# minidoxs.net
KiCad netlist of a schematic drawn in EAGLE
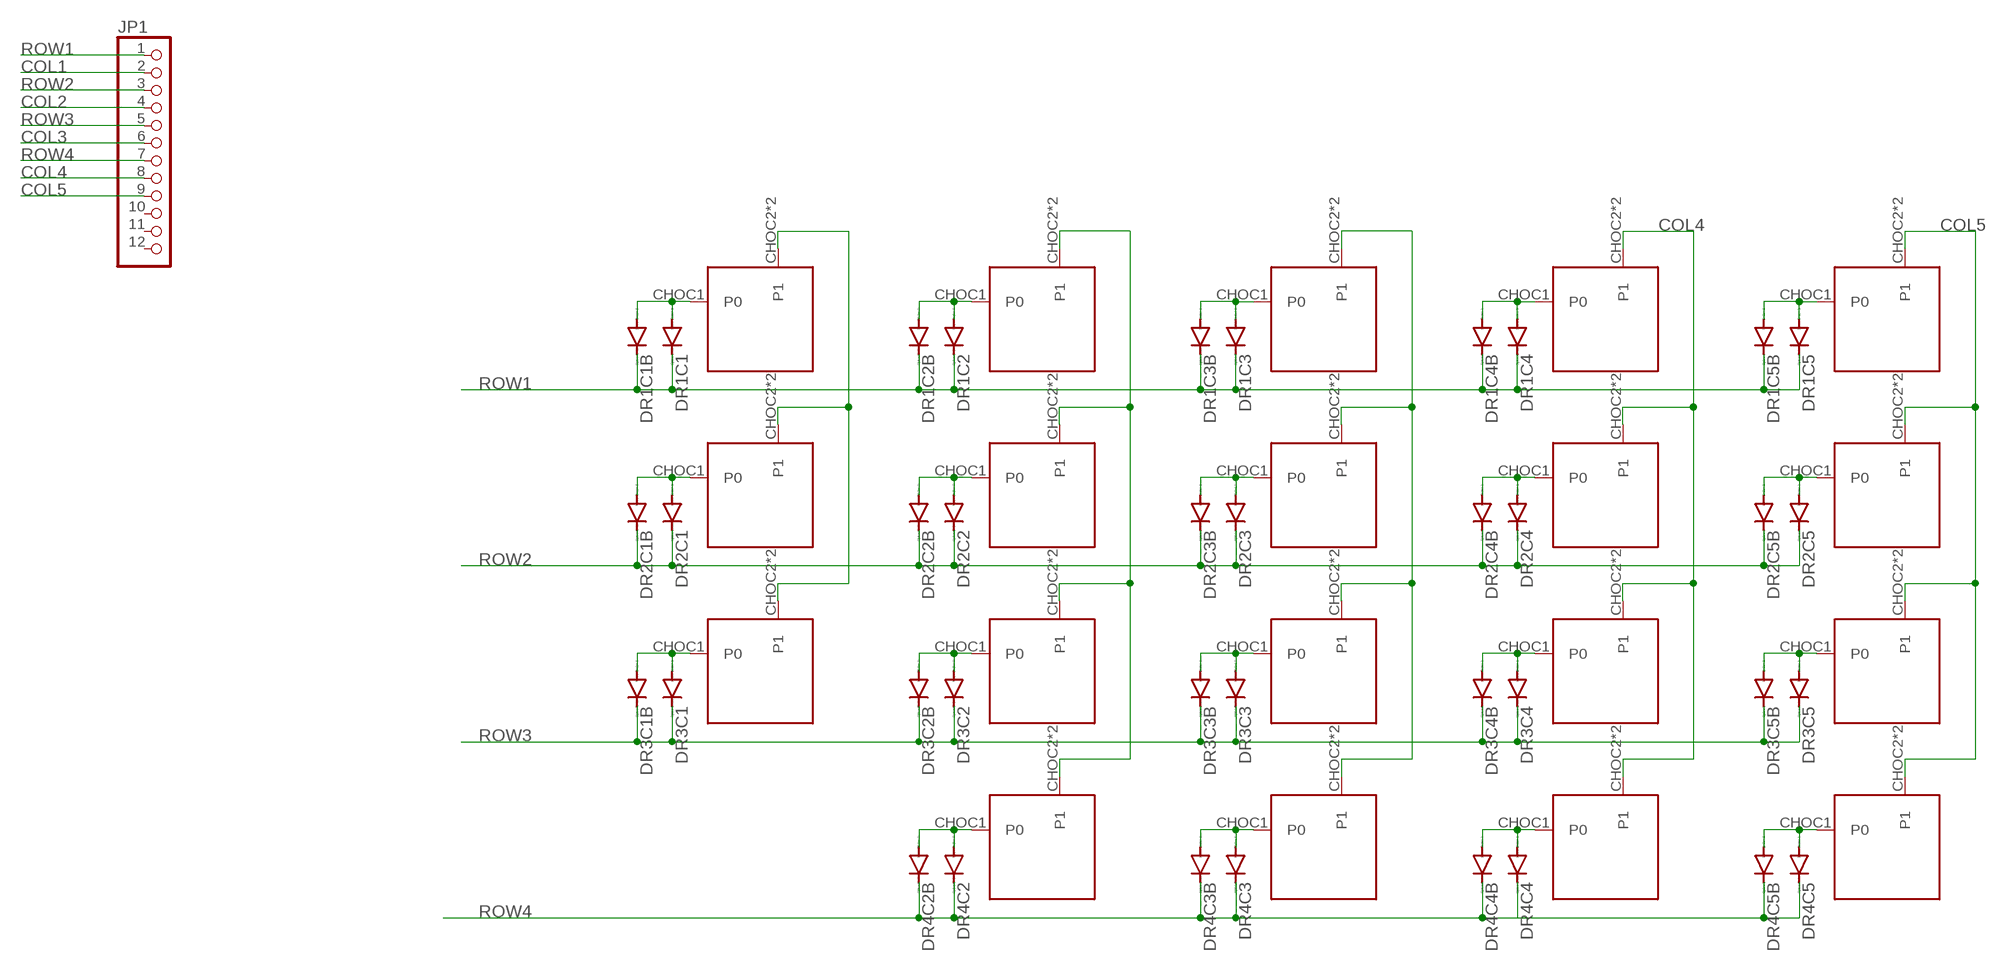
[diagram p0: schematic, sheet 1]

(export (version "E")
  (design (tool "Eeschema 10.0.6"))
  (components
    (comp (ref "DR1C1")
      (value "MBR0520LT")
      (footprint "eagle-import:SOD123")
      (libsource (lib "eagle-import") (part "MBR0520LT"))
    )
    (comp (ref "DR1C1B")
      (value "MBR0520LT")
      (footprint "eagle-import:SOD123")
      (libsource (lib "eagle-import") (part "MBR0520LT"))
    )
    (comp (ref "DR1C2")
      (value "MBR0520LT")
      (footprint "eagle-import:SOD123")
      (libsource (lib "eagle-import") (part "MBR0520LT"))
    )
    (comp (ref "DR1C2B")
      (value "MBR0520LT")
      (footprint "eagle-import:SOD123")
      (libsource (lib "eagle-import") (part "MBR0520LT"))
    )
    (comp (ref "DR1C3")
      (value "MBR0520LT")
      (footprint "eagle-import:SOD123")
      (libsource (lib "eagle-import") (part "MBR0520LT"))
    )
    (comp (ref "DR1C3B")
      (value "MBR0520LT")
      (footprint "eagle-import:SOD123")
      (libsource (lib "eagle-import") (part "MBR0520LT"))
    )
    (comp (ref "DR1C4")
      (value "MBR0520LT")
      (footprint "eagle-import:SOD123")
      (libsource (lib "eagle-import") (part "MBR0520LT"))
    )
    (comp (ref "DR1C4B")
      (value "MBR0520LT")
      (footprint "eagle-import:SOD123")
      (libsource (lib "eagle-import") (part "MBR0520LT"))
    )
    (comp (ref "DR1C5")
      (value "MBR0520LT")
      (footprint "eagle-import:SOD123")
      (libsource (lib "eagle-import") (part "MBR0520LT"))
    )
    (comp (ref "DR1C5B")
      (value "MBR0520LT")
      (footprint "eagle-import:SOD123")
      (libsource (lib "eagle-import") (part "MBR0520LT"))
    )
    (comp (ref "DR2C1")
      (value "MBR0520LT")
      (footprint "eagle-import:SOD123")
      (libsource (lib "eagle-import") (part "MBR0520LT"))
    )
    (comp (ref "DR2C1B")
      (value "MBR0520LT")
      (footprint "eagle-import:SOD123")
      (libsource (lib "eagle-import") (part "MBR0520LT"))
    )
    (comp (ref "DR2C2")
      (value "MBR0520LT")
      (footprint "eagle-import:SOD123")
      (libsource (lib "eagle-import") (part "MBR0520LT"))
    )
    (comp (ref "DR2C2B")
      (value "MBR0520LT")
      (footprint "eagle-import:SOD123")
      (libsource (lib "eagle-import") (part "MBR0520LT"))
    )
    (comp (ref "DR2C3")
      (value "MBR0520LT")
      (footprint "eagle-import:SOD123")
      (libsource (lib "eagle-import") (part "MBR0520LT"))
    )
    (comp (ref "DR2C3B")
      (value "MBR0520LT")
      (footprint "eagle-import:SOD123")
      (libsource (lib "eagle-import") (part "MBR0520LT"))
    )
    (comp (ref "DR2C4")
      (value "MBR0520LT")
      (footprint "eagle-import:SOD123")
      (libsource (lib "eagle-import") (part "MBR0520LT"))
    )
    (comp (ref "DR2C4B")
      (value "MBR0520LT")
      (footprint "eagle-import:SOD123")
      (libsource (lib "eagle-import") (part "MBR0520LT"))
    )
    (comp (ref "DR2C5")
      (value "MBR0520LT")
      (footprint "eagle-import:SOD123")
      (libsource (lib "eagle-import") (part "MBR0520LT"))
    )
    (comp (ref "DR2C5B")
      (value "MBR0520LT")
      (footprint "eagle-import:SOD123")
      (libsource (lib "eagle-import") (part "MBR0520LT"))
    )
    (comp (ref "DR3C1")
      (value "MBR0520LT")
      (footprint "eagle-import:SOD123")
      (libsource (lib "eagle-import") (part "MBR0520LT"))
    )
    (comp (ref "DR3C1B")
      (value "MBR0520LT")
      (footprint "eagle-import:SOD123")
      (libsource (lib "eagle-import") (part "MBR0520LT"))
    )
    (comp (ref "DR3C2")
      (value "MBR0520LT")
      (footprint "eagle-import:SOD123")
      (libsource (lib "eagle-import") (part "MBR0520LT"))
    )
    (comp (ref "DR3C2B")
      (value "MBR0520LT")
      (footprint "eagle-import:SOD123")
      (libsource (lib "eagle-import") (part "MBR0520LT"))
    )
    (comp (ref "DR3C3")
      (value "MBR0520LT")
      (footprint "eagle-import:SOD123")
      (libsource (lib "eagle-import") (part "MBR0520LT"))
    )
    (comp (ref "DR3C3B")
      (value "MBR0520LT")
      (footprint "eagle-import:SOD123")
      (libsource (lib "eagle-import") (part "MBR0520LT"))
    )
    (comp (ref "DR3C4")
      (value "MBR0520LT")
      (footprint "eagle-import:SOD123")
      (libsource (lib "eagle-import") (part "MBR0520LT"))
    )
    (comp (ref "DR3C4B")
      (value "MBR0520LT")
      (footprint "eagle-import:SOD123")
      (libsource (lib "eagle-import") (part "MBR0520LT"))
    )
    (comp (ref "DR3C5")
      (value "MBR0520LT")
      (footprint "eagle-import:SOD123")
      (libsource (lib "eagle-import") (part "MBR0520LT"))
    )
    (comp (ref "DR3C5B")
      (value "MBR0520LT")
      (footprint "eagle-import:SOD123")
      (libsource (lib "eagle-import") (part "MBR0520LT"))
    )
    (comp (ref "DR4C2")
      (value "MBR0520LT")
      (footprint "eagle-import:SOD123")
      (libsource (lib "eagle-import") (part "MBR0520LT"))
    )
    (comp (ref "DR4C2B")
      (value "MBR0520LT")
      (footprint "eagle-import:SOD123")
      (libsource (lib "eagle-import") (part "MBR0520LT"))
    )
    (comp (ref "DR4C3")
      (value "MBR0520LT")
      (footprint "eagle-import:SOD123")
      (libsource (lib "eagle-import") (part "MBR0520LT"))
    )
    (comp (ref "DR4C3B")
      (value "MBR0520LT")
      (footprint "eagle-import:SOD123")
      (libsource (lib "eagle-import") (part "MBR0520LT"))
    )
    (comp (ref "DR4C4")
      (value "MBR0520LT")
      (footprint "eagle-import:SOD123")
      (libsource (lib "eagle-import") (part "MBR0520LT"))
    )
    (comp (ref "DR4C4B")
      (value "MBR0520LT")
      (footprint "eagle-import:SOD123")
      (libsource (lib "eagle-import") (part "MBR0520LT"))
    )
    (comp (ref "DR4C5")
      (value "MBR0520LT")
      (footprint "eagle-import:SOD123")
      (libsource (lib "eagle-import") (part "MBR0520LT"))
    )
    (comp (ref "DR4C5B")
      (value "MBR0520LT")
      (footprint "eagle-import:SOD123")
      (libsource (lib "eagle-import") (part "MBR0520LT"))
    )
    (comp (ref "JP1")
      (value "PINHD-1X12")
      (footprint "eagle-import:1X12")
      (libsource (lib "eagle-import") (part "PINHD-1X12"))
    )
    (comp (ref "U$R1C1")
      (value "KEYSWITCH-PLAIN-CHOC-1U")
      (footprint "eagle-import:CHOC-1U")
      (libsource (lib "eagle-import") (part "KEYSWITCH-PLAIN-CHOC-1U"))
    )
    (comp (ref "U$R1C2")
      (value "KEYSWITCH-PLAIN-CHOC-1U")
      (footprint "eagle-import:CHOC-1U")
      (libsource (lib "eagle-import") (part "KEYSWITCH-PLAIN-CHOC-1U"))
    )
    (comp (ref "U$R1C3")
      (value "KEYSWITCH-PLAIN-CHOC-1U")
      (footprint "eagle-import:CHOC-1U")
      (libsource (lib "eagle-import") (part "KEYSWITCH-PLAIN-CHOC-1U"))
    )
    (comp (ref "U$R1C4")
      (value "KEYSWITCH-PLAIN-CHOC-1U")
      (footprint "eagle-import:CHOC-1U")
      (libsource (lib "eagle-import") (part "KEYSWITCH-PLAIN-CHOC-1U"))
    )
    (comp (ref "U$R1C5")
      (value "KEYSWITCH-PLAIN-CHOC-1U")
      (footprint "eagle-import:CHOC-1U")
      (libsource (lib "eagle-import") (part "KEYSWITCH-PLAIN-CHOC-1U"))
    )
    (comp (ref "U$R2C1")
      (value "KEYSWITCH-PLAIN-CHOC-1U")
      (footprint "eagle-import:CHOC-1U")
      (libsource (lib "eagle-import") (part "KEYSWITCH-PLAIN-CHOC-1U"))
    )
    (comp (ref "U$R2C2")
      (value "KEYSWITCH-PLAIN-CHOC-1U")
      (footprint "eagle-import:CHOC-1U")
      (libsource (lib "eagle-import") (part "KEYSWITCH-PLAIN-CHOC-1U"))
    )
    (comp (ref "U$R2C3")
      (value "KEYSWITCH-PLAIN-CHOC-1U")
      (footprint "eagle-import:CHOC-1U")
      (libsource (lib "eagle-import") (part "KEYSWITCH-PLAIN-CHOC-1U"))
    )
    (comp (ref "U$R2C4")
      (value "KEYSWITCH-PLAIN-CHOC-1U")
      (footprint "eagle-import:CHOC-1U")
      (libsource (lib "eagle-import") (part "KEYSWITCH-PLAIN-CHOC-1U"))
    )
    (comp (ref "U$R2C5")
      (value "KEYSWITCH-PLAIN-CHOC-1U")
      (footprint "eagle-import:CHOC-1U")
      (libsource (lib "eagle-import") (part "KEYSWITCH-PLAIN-CHOC-1U"))
    )
    (comp (ref "U$R3C1")
      (value "KEYSWITCH-PLAIN-CHOC-1U")
      (footprint "eagle-import:CHOC-1U")
      (libsource (lib "eagle-import") (part "KEYSWITCH-PLAIN-CHOC-1U"))
    )
    (comp (ref "U$R3C2")
      (value "KEYSWITCH-PLAIN-CHOC-1U")
      (footprint "eagle-import:CHOC-1U")
      (libsource (lib "eagle-import") (part "KEYSWITCH-PLAIN-CHOC-1U"))
    )
    (comp (ref "U$R3C3")
      (value "KEYSWITCH-PLAIN-CHOC-1U")
      (footprint "eagle-import:CHOC-1U")
      (libsource (lib "eagle-import") (part "KEYSWITCH-PLAIN-CHOC-1U"))
    )
    (comp (ref "U$R3C4")
      (value "KEYSWITCH-PLAIN-CHOC-1U")
      (footprint "eagle-import:CHOC-1U")
      (libsource (lib "eagle-import") (part "KEYSWITCH-PLAIN-CHOC-1U"))
    )
    (comp (ref "U$R3C5")
      (value "KEYSWITCH-PLAIN-CHOC-1U")
      (footprint "eagle-import:CHOC-1U")
      (libsource (lib "eagle-import") (part "KEYSWITCH-PLAIN-CHOC-1U"))
    )
    (comp (ref "U$R4C2")
      (value "KEYSWITCH-PLAIN-CHOC-1U")
      (footprint "eagle-import:CHOC-1U")
      (libsource (lib "eagle-import") (part "KEYSWITCH-PLAIN-CHOC-1U"))
    )
    (comp (ref "U$R4C3")
      (value "KEYSWITCH-PLAIN-CHOC-1U")
      (footprint "eagle-import:CHOC-1U")
      (libsource (lib "eagle-import") (part "KEYSWITCH-PLAIN-CHOC-1U"))
    )
    (comp (ref "U$R4C4")
      (value "KEYSWITCH-PLAIN-CHOC-1U")
      (footprint "eagle-import:CHOC-1U")
      (libsource (lib "eagle-import") (part "KEYSWITCH-PLAIN-CHOC-1U"))
    )
    (comp (ref "U$R4C5")
      (value "KEYSWITCH-PLAIN-CHOC-1U")
      (footprint "eagle-import:CHOC-1U")
      (libsource (lib "eagle-import") (part "KEYSWITCH-PLAIN-CHOC-1U"))
    )
  )
  (nets
    (net (code "1") (name "/COL1") (class "Default")
      (node (ref "JP1") (pin "2") (pinfunction "2_2") (pintype "passive"))
      (node (ref "U$R1C1") (pin "CHOC2") (pinfunction "P1_CHOC2") (pintype "bidirectional"))
      (node (ref "U$R1C1") (pin "CHOC3") (pinfunction "P1_CHOC3") (pintype "bidirectional"))
      (node (ref "U$R2C1") (pin "CHOC2") (pinfunction "P1_CHOC2") (pintype "bidirectional"))
      (node (ref "U$R2C1") (pin "CHOC3") (pinfunction "P1_CHOC3") (pintype "bidirectional"))
      (node (ref "U$R3C1") (pin "CHOC2") (pinfunction "P1_CHOC2") (pintype "bidirectional"))
      (node (ref "U$R3C1") (pin "CHOC3") (pinfunction "P1_CHOC3") (pintype "bidirectional"))
    )
    (net (code "2") (name "/COL2") (class "Default")
      (node (ref "JP1") (pin "4") (pinfunction "4_4") (pintype "passive"))
      (node (ref "U$R1C2") (pin "CHOC2") (pinfunction "P1_CHOC2") (pintype "bidirectional"))
      (node (ref "U$R1C2") (pin "CHOC3") (pinfunction "P1_CHOC3") (pintype "bidirectional"))
      (node (ref "U$R2C2") (pin "CHOC2") (pinfunction "P1_CHOC2") (pintype "bidirectional"))
      (node (ref "U$R2C2") (pin "CHOC3") (pinfunction "P1_CHOC3") (pintype "bidirectional"))
      (node (ref "U$R3C2") (pin "CHOC2") (pinfunction "P1_CHOC2") (pintype "bidirectional"))
      (node (ref "U$R3C2") (pin "CHOC3") (pinfunction "P1_CHOC3") (pintype "bidirectional"))
      (node (ref "U$R4C2") (pin "CHOC2") (pinfunction "P1_CHOC2") (pintype "bidirectional"))
      (node (ref "U$R4C2") (pin "CHOC3") (pinfunction "P1_CHOC3") (pintype "bidirectional"))
    )
    (net (code "3") (name "/COL3") (class "Default")
      (node (ref "JP1") (pin "6") (pinfunction "6_6") (pintype "passive"))
      (node (ref "U$R1C3") (pin "CHOC2") (pinfunction "P1_CHOC2") (pintype "bidirectional"))
      (node (ref "U$R1C3") (pin "CHOC3") (pinfunction "P1_CHOC3") (pintype "bidirectional"))
      (node (ref "U$R2C3") (pin "CHOC2") (pinfunction "P1_CHOC2") (pintype "bidirectional"))
      (node (ref "U$R2C3") (pin "CHOC3") (pinfunction "P1_CHOC3") (pintype "bidirectional"))
      (node (ref "U$R3C3") (pin "CHOC2") (pinfunction "P1_CHOC2") (pintype "bidirectional"))
      (node (ref "U$R3C3") (pin "CHOC3") (pinfunction "P1_CHOC3") (pintype "bidirectional"))
      (node (ref "U$R4C3") (pin "CHOC2") (pinfunction "P1_CHOC2") (pintype "bidirectional"))
      (node (ref "U$R4C3") (pin "CHOC3") (pinfunction "P1_CHOC3") (pintype "bidirectional"))
    )
    (net (code "4") (name "/COL4") (class "Default")
      (node (ref "JP1") (pin "8") (pinfunction "8_8") (pintype "passive"))
      (node (ref "U$R1C4") (pin "CHOC2") (pinfunction "P1_CHOC2") (pintype "bidirectional"))
      (node (ref "U$R1C4") (pin "CHOC3") (pinfunction "P1_CHOC3") (pintype "bidirectional"))
      (node (ref "U$R2C4") (pin "CHOC2") (pinfunction "P1_CHOC2") (pintype "bidirectional"))
      (node (ref "U$R2C4") (pin "CHOC3") (pinfunction "P1_CHOC3") (pintype "bidirectional"))
      (node (ref "U$R3C4") (pin "CHOC2") (pinfunction "P1_CHOC2") (pintype "bidirectional"))
      (node (ref "U$R3C4") (pin "CHOC3") (pinfunction "P1_CHOC3") (pintype "bidirectional"))
      (node (ref "U$R4C4") (pin "CHOC2") (pinfunction "P1_CHOC2") (pintype "bidirectional"))
      (node (ref "U$R4C4") (pin "CHOC3") (pinfunction "P1_CHOC3") (pintype "bidirectional"))
    )
    (net (code "5") (name "/COL5") (class "Default")
      (node (ref "JP1") (pin "9") (pinfunction "9_9") (pintype "passive"))
      (node (ref "U$R1C5") (pin "CHOC2") (pinfunction "P1_CHOC2") (pintype "bidirectional"))
      (node (ref "U$R1C5") (pin "CHOC3") (pinfunction "P1_CHOC3") (pintype "bidirectional"))
      (node (ref "U$R2C5") (pin "CHOC2") (pinfunction "P1_CHOC2") (pintype "bidirectional"))
      (node (ref "U$R2C5") (pin "CHOC3") (pinfunction "P1_CHOC3") (pintype "bidirectional"))
      (node (ref "U$R3C5") (pin "CHOC2") (pinfunction "P1_CHOC2") (pintype "bidirectional"))
      (node (ref "U$R3C5") (pin "CHOC3") (pinfunction "P1_CHOC3") (pintype "bidirectional"))
      (node (ref "U$R4C5") (pin "CHOC2") (pinfunction "P1_CHOC2") (pintype "bidirectional"))
      (node (ref "U$R4C5") (pin "CHOC3") (pinfunction "P1_CHOC3") (pintype "bidirectional"))
    )
    (net (code "6") (name "/ROW1") (class "Default")
      (node (ref "DR1C1") (pin "C") (pinfunction "C_C") (pintype "passive"))
      (node (ref "DR1C1B") (pin "C") (pinfunction "C_C") (pintype "passive"))
      (node (ref "DR1C2") (pin "C") (pinfunction "C_C") (pintype "passive"))
      (node (ref "DR1C2B") (pin "C") (pinfunction "C_C") (pintype "passive"))
      (node (ref "DR1C3") (pin "C") (pinfunction "C_C") (pintype "passive"))
      (node (ref "DR1C3B") (pin "C") (pinfunction "C_C") (pintype "passive"))
      (node (ref "DR1C4") (pin "C") (pinfunction "C_C") (pintype "passive"))
      (node (ref "DR1C4B") (pin "C") (pinfunction "C_C") (pintype "passive"))
      (node (ref "DR1C5") (pin "C") (pinfunction "C_C") (pintype "passive"))
      (node (ref "DR1C5B") (pin "C") (pinfunction "C_C") (pintype "passive"))
      (node (ref "JP1") (pin "1") (pinfunction "1_1") (pintype "passive"))
    )
    (net (code "7") (name "/ROW2") (class "Default")
      (node (ref "DR2C1") (pin "C") (pinfunction "C_C") (pintype "passive"))
      (node (ref "DR2C1B") (pin "C") (pinfunction "C_C") (pintype "passive"))
      (node (ref "DR2C2") (pin "C") (pinfunction "C_C") (pintype "passive"))
      (node (ref "DR2C2B") (pin "C") (pinfunction "C_C") (pintype "passive"))
      (node (ref "DR2C3") (pin "C") (pinfunction "C_C") (pintype "passive"))
      (node (ref "DR2C3B") (pin "C") (pinfunction "C_C") (pintype "passive"))
      (node (ref "DR2C4") (pin "C") (pinfunction "C_C") (pintype "passive"))
      (node (ref "DR2C4B") (pin "C") (pinfunction "C_C") (pintype "passive"))
      (node (ref "DR2C5") (pin "C") (pinfunction "C_C") (pintype "passive"))
      (node (ref "DR2C5B") (pin "C") (pinfunction "C_C") (pintype "passive"))
      (node (ref "JP1") (pin "3") (pinfunction "3_3") (pintype "passive"))
    )
    (net (code "8") (name "/ROW3") (class "Default")
      (node (ref "DR3C1") (pin "C") (pinfunction "C_C") (pintype "passive"))
      (node (ref "DR3C1B") (pin "C") (pinfunction "C_C") (pintype "passive"))
      (node (ref "DR3C2") (pin "C") (pinfunction "C_C") (pintype "passive"))
      (node (ref "DR3C2B") (pin "C") (pinfunction "C_C") (pintype "passive"))
      (node (ref "DR3C3") (pin "C") (pinfunction "C_C") (pintype "passive"))
      (node (ref "DR3C3B") (pin "C") (pinfunction "C_C") (pintype "passive"))
      (node (ref "DR3C4") (pin "C") (pinfunction "C_C") (pintype "passive"))
      (node (ref "DR3C4B") (pin "C") (pinfunction "C_C") (pintype "passive"))
      (node (ref "DR3C5") (pin "C") (pinfunction "C_C") (pintype "passive"))
      (node (ref "DR3C5B") (pin "C") (pinfunction "C_C") (pintype "passive"))
      (node (ref "JP1") (pin "5") (pinfunction "5_5") (pintype "passive"))
    )
    (net (code "9") (name "/ROW4") (class "Default")
      (node (ref "DR4C2") (pin "C") (pinfunction "C_C") (pintype "passive"))
      (node (ref "DR4C2B") (pin "C") (pinfunction "C_C") (pintype "passive"))
      (node (ref "DR4C3") (pin "C") (pinfunction "C_C") (pintype "passive"))
      (node (ref "DR4C3B") (pin "C") (pinfunction "C_C") (pintype "passive"))
      (node (ref "DR4C4") (pin "C") (pinfunction "C_C") (pintype "passive"))
      (node (ref "DR4C4B") (pin "C") (pinfunction "C_C") (pintype "passive"))
      (node (ref "DR4C5") (pin "C") (pinfunction "C_C") (pintype "passive"))
      (node (ref "DR4C5B") (pin "C") (pinfunction "C_C") (pintype "passive"))
      (node (ref "JP1") (pin "7") (pinfunction "7_7") (pintype "passive"))
    )
    (net (code "10") (name "Net-(U$R1C1-P0)") (class "Default")
      (node (ref "DR1C1") (pin "A") (pinfunction "A_A") (pintype "passive"))
      (node (ref "DR1C1B") (pin "A") (pinfunction "A_A") (pintype "passive"))
      (node (ref "U$R1C1") (pin "CHOC1") (pinfunction "P0_CHOC1") (pintype "bidirectional"))
    )
    (net (code "11") (name "Net-(U$R1C2-P0)") (class "Default")
      (node (ref "DR1C2") (pin "A") (pinfunction "A_A") (pintype "passive"))
      (node (ref "DR1C2B") (pin "A") (pinfunction "A_A") (pintype "passive"))
      (node (ref "U$R1C2") (pin "CHOC1") (pinfunction "P0_CHOC1") (pintype "bidirectional"))
    )
    (net (code "12") (name "Net-(U$R1C3-P0)") (class "Default")
      (node (ref "DR1C3") (pin "A") (pinfunction "A_A") (pintype "passive"))
      (node (ref "DR1C3B") (pin "A") (pinfunction "A_A") (pintype "passive"))
      (node (ref "U$R1C3") (pin "CHOC1") (pinfunction "P0_CHOC1") (pintype "bidirectional"))
    )
    (net (code "13") (name "Net-(U$R1C4-P0)") (class "Default")
      (node (ref "DR1C4") (pin "A") (pinfunction "A_A") (pintype "passive"))
      (node (ref "DR1C4B") (pin "A") (pinfunction "A_A") (pintype "passive"))
      (node (ref "U$R1C4") (pin "CHOC1") (pinfunction "P0_CHOC1") (pintype "bidirectional"))
    )
    (net (code "14") (name "Net-(U$R1C5-P0)") (class "Default")
      (node (ref "DR1C5") (pin "A") (pinfunction "A_A") (pintype "passive"))
      (node (ref "DR1C5B") (pin "A") (pinfunction "A_A") (pintype "passive"))
      (node (ref "U$R1C5") (pin "CHOC1") (pinfunction "P0_CHOC1") (pintype "bidirectional"))
    )
    (net (code "15") (name "Net-(U$R2C1-P0)") (class "Default")
      (node (ref "DR2C1") (pin "A") (pinfunction "A_A") (pintype "passive"))
      (node (ref "DR2C1B") (pin "A") (pinfunction "A_A") (pintype "passive"))
      (node (ref "U$R2C1") (pin "CHOC1") (pinfunction "P0_CHOC1") (pintype "bidirectional"))
    )
    (net (code "16") (name "Net-(U$R2C2-P0)") (class "Default")
      (node (ref "DR2C2") (pin "A") (pinfunction "A_A") (pintype "passive"))
      (node (ref "DR2C2B") (pin "A") (pinfunction "A_A") (pintype "passive"))
      (node (ref "U$R2C2") (pin "CHOC1") (pinfunction "P0_CHOC1") (pintype "bidirectional"))
    )
    (net (code "17") (name "Net-(U$R2C3-P0)") (class "Default")
      (node (ref "DR2C3") (pin "A") (pinfunction "A_A") (pintype "passive"))
      (node (ref "DR2C3B") (pin "A") (pinfunction "A_A") (pintype "passive"))
      (node (ref "U$R2C3") (pin "CHOC1") (pinfunction "P0_CHOC1") (pintype "bidirectional"))
    )
    (net (code "18") (name "Net-(U$R2C4-P0)") (class "Default")
      (node (ref "DR2C4") (pin "A") (pinfunction "A_A") (pintype "passive"))
      (node (ref "DR2C4B") (pin "A") (pinfunction "A_A") (pintype "passive"))
      (node (ref "U$R2C4") (pin "CHOC1") (pinfunction "P0_CHOC1") (pintype "bidirectional"))
    )
    (net (code "19") (name "Net-(U$R2C5-P0)") (class "Default")
      (node (ref "DR2C5") (pin "A") (pinfunction "A_A") (pintype "passive"))
      (node (ref "DR2C5B") (pin "A") (pinfunction "A_A") (pintype "passive"))
      (node (ref "U$R2C5") (pin "CHOC1") (pinfunction "P0_CHOC1") (pintype "bidirectional"))
    )
    (net (code "20") (name "Net-(U$R3C1-P0)") (class "Default")
      (node (ref "DR3C1") (pin "A") (pinfunction "A_A") (pintype "passive"))
      (node (ref "DR3C1B") (pin "A") (pinfunction "A_A") (pintype "passive"))
      (node (ref "U$R3C1") (pin "CHOC1") (pinfunction "P0_CHOC1") (pintype "bidirectional"))
    )
    (net (code "21") (name "Net-(U$R3C2-P0)") (class "Default")
      (node (ref "DR3C2") (pin "A") (pinfunction "A_A") (pintype "passive"))
      (node (ref "DR3C2B") (pin "A") (pinfunction "A_A") (pintype "passive"))
      (node (ref "U$R3C2") (pin "CHOC1") (pinfunction "P0_CHOC1") (pintype "bidirectional"))
    )
    (net (code "22") (name "Net-(U$R3C3-P0)") (class "Default")
      (node (ref "DR3C3") (pin "A") (pinfunction "A_A") (pintype "passive"))
      (node (ref "DR3C3B") (pin "A") (pinfunction "A_A") (pintype "passive"))
      (node (ref "U$R3C3") (pin "CHOC1") (pinfunction "P0_CHOC1") (pintype "bidirectional"))
    )
    (net (code "23") (name "Net-(U$R3C4-P0)") (class "Default")
      (node (ref "DR3C4") (pin "A") (pinfunction "A_A") (pintype "passive"))
      (node (ref "DR3C4B") (pin "A") (pinfunction "A_A") (pintype "passive"))
      (node (ref "U$R3C4") (pin "CHOC1") (pinfunction "P0_CHOC1") (pintype "bidirectional"))
    )
    (net (code "24") (name "Net-(U$R3C5-P0)") (class "Default")
      (node (ref "DR3C5") (pin "A") (pinfunction "A_A") (pintype "passive"))
      (node (ref "DR3C5B") (pin "A") (pinfunction "A_A") (pintype "passive"))
      (node (ref "U$R3C5") (pin "CHOC1") (pinfunction "P0_CHOC1") (pintype "bidirectional"))
    )
    (net (code "25") (name "Net-(U$R4C2-P0)") (class "Default")
      (node (ref "DR4C2") (pin "A") (pinfunction "A_A") (pintype "passive"))
      (node (ref "DR4C2B") (pin "A") (pinfunction "A_A") (pintype "passive"))
      (node (ref "U$R4C2") (pin "CHOC1") (pinfunction "P0_CHOC1") (pintype "bidirectional"))
    )
    (net (code "26") (name "Net-(U$R4C3-P0)") (class "Default")
      (node (ref "DR4C3") (pin "A") (pinfunction "A_A") (pintype "passive"))
      (node (ref "DR4C3B") (pin "A") (pinfunction "A_A") (pintype "passive"))
      (node (ref "U$R4C3") (pin "CHOC1") (pinfunction "P0_CHOC1") (pintype "bidirectional"))
    )
    (net (code "27") (name "Net-(U$R4C4-P0)") (class "Default")
      (node (ref "DR4C4") (pin "A") (pinfunction "A_A") (pintype "passive"))
      (node (ref "DR4C4B") (pin "A") (pinfunction "A_A") (pintype "passive"))
      (node (ref "U$R4C4") (pin "CHOC1") (pinfunction "P0_CHOC1") (pintype "bidirectional"))
    )
    (net (code "28") (name "Net-(U$R4C5-P0)") (class "Default")
      (node (ref "DR4C5") (pin "A") (pinfunction "A_A") (pintype "passive"))
      (node (ref "DR4C5B") (pin "A") (pinfunction "A_A") (pintype "passive"))
      (node (ref "U$R4C5") (pin "CHOC1") (pinfunction "P0_CHOC1") (pintype "bidirectional"))
    )
    (net (code "29") (name "unconnected-(JP1-Pad10)") (class "Default")
      (node (ref "JP1") (pin "10") (pinfunction "10_10") (pintype "passive"))
    )
    (net (code "30") (name "unconnected-(JP1-Pad11)") (class "Default")
      (node (ref "JP1") (pin "11") (pinfunction "11_11") (pintype "passive"))
    )
    (net (code "31") (name "unconnected-(JP1-Pad12)") (class "Default")
      (node (ref "JP1") (pin "12") (pinfunction "12_12") (pintype "passive"))
    )
  )
)
